# Sheet1.net
KiCad netlist of a schematic drawn in Altium Designer
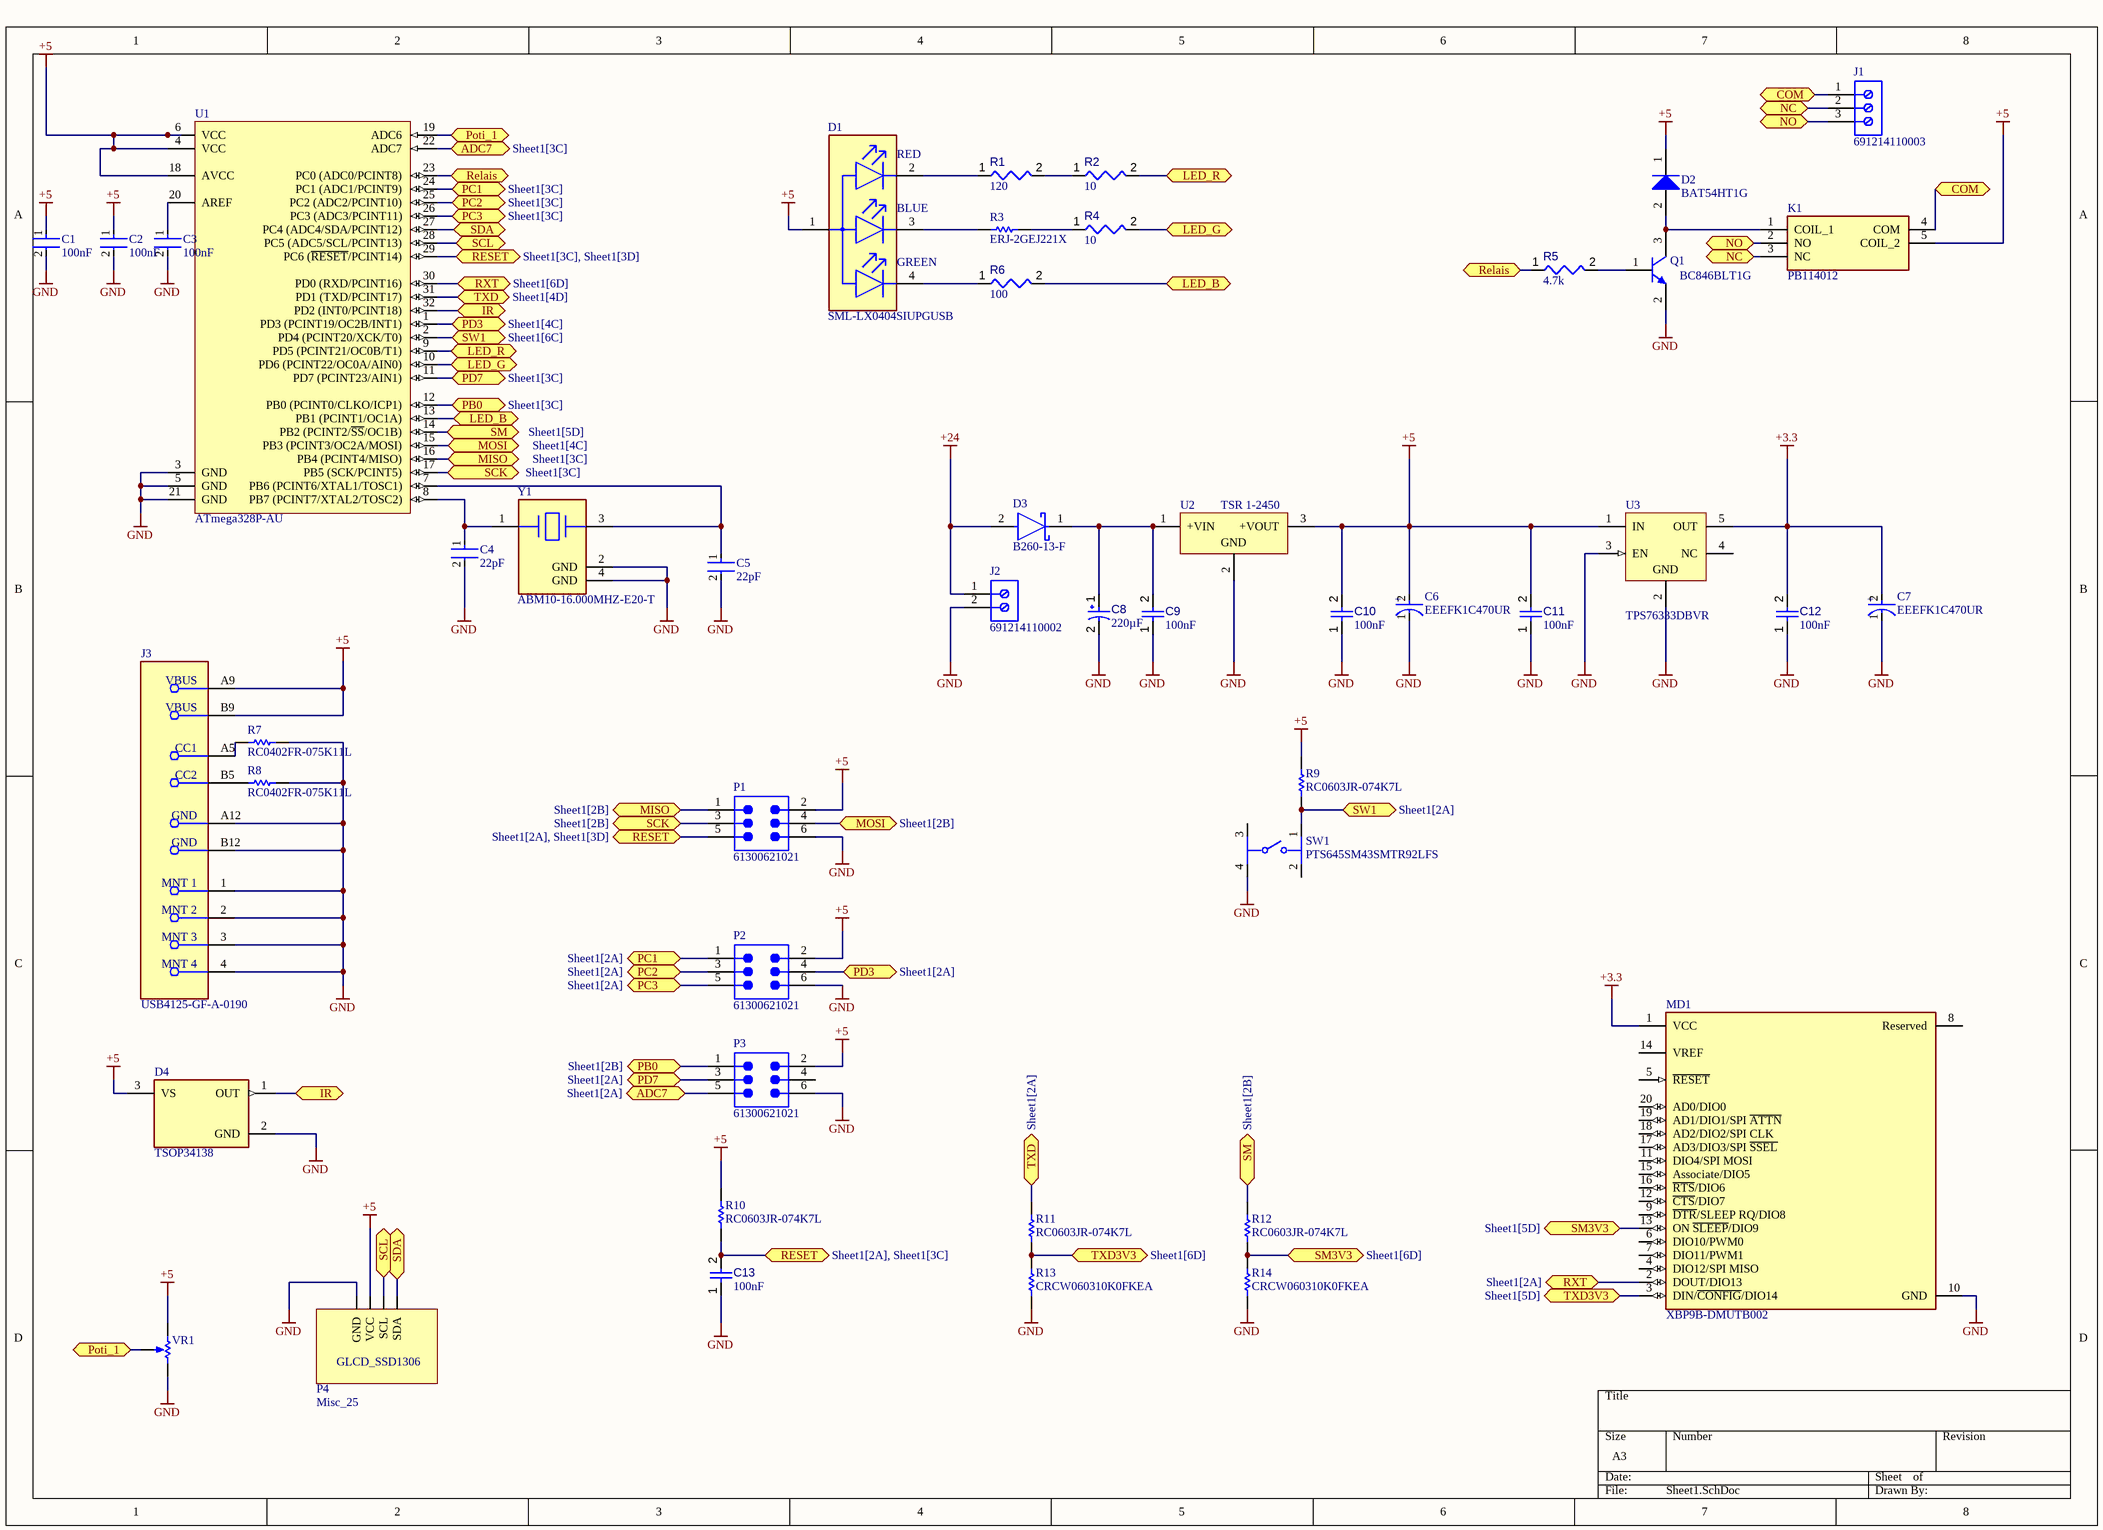
[diagram p0: Sheet1.SchDoc]

(export (version "E")
  (design (tool "Eeschema 10.0.6"))
  (components
    (comp (ref "C1")
      (value "100nF")
      (footprint "FP-C0805C-DN-MFG")
      (description "CAP CER 0.1UF 50V X7R 0805")
      (fields
        (field (name "MANUFACTURER PART NUMBER") "C0805C104K5RACTU")
        (field (name "MANUFACTURER") "KEMET")
      )
      (libsource (lib "Altium Content Vault") (part "b4654b650e69147ec39a6b967a45e02"))
    )
    (comp (ref "C2")
      (value "100nF")
      (footprint "FP-C0805C-DN-MFG")
      (description "CAP CER 0.1UF 50V X7R 0805")
      (fields
        (field (name "MANUFACTURER PART NUMBER") "C0805C104K5RACTU")
        (field (name "MANUFACTURER") "KEMET")
      )
      (libsource (lib "Altium Content Vault") (part "b4654b650e69147ec39a6b967a45e02"))
    )
    (comp (ref "C3")
      (value "100nF")
      (footprint "FP-C0805C-DN-MFG")
      (description "CAP CER 0.1UF 50V X7R 0805")
      (fields
        (field (name "MANUFACTURER PART NUMBER") "C0805C104K5RACTU")
        (field (name "MANUFACTURER") "KEMET")
      )
      (libsource (lib "Altium Content Vault") (part "b4654b650e69147ec39a6b967a45e02"))
    )
    (comp (ref "C4")
      (value "22pF")
      (footprint "FP-C0805C-DN-MFG")
      (description "Capacitor; Ceramic; Cap; 22.0pF; Tol 5%; SMT; Vol-Rtg 50V; C0G; Tape and Reel")
      (fields
        (field (name "OCTOPART") "https://octopart.com/c0805c220j5gactu-kemet-145470")
        (field (name "MANUFACTURER") "KEMET")
      )
      (libsource (lib "Altium Content Vault") (part "b4654b650e69147ec39a6b967a45e02"))
    )
    (comp (ref "C5")
      (value "22pF")
      (footprint "FP-C0805C-DN-MFG")
      (description "Capacitor; Ceramic; Cap; 22.0pF; Tol 5%; SMT; Vol-Rtg 50V; C0G; Tape and Reel")
      (fields
        (field (name "OCTOPART") "https://octopart.com/c0805c220j5gactu-kemet-145470")
        (field (name "MANUFACTURER") "KEMET")
      )
      (libsource (lib "Altium Content Vault") (part "b4654b650e69147ec39a6b967a45e02"))
    )
    (comp (ref "C6")
      (value "EEEFK1C470UR")
      (footprint "FP-FKC-MFG")
      (description "CAP ALUM 47UF 20% 16V SMD")
      (fields (field (name "VOLTAGE") "10V") (field (name "TOLERANCE") "20%"))
      (libsource (lib "Altium Content Vault") (part "cf48714ba7e38822c1575c7ec0b6d1f"))
    )
    (comp (ref "C7")
      (value "EEEFK1C470UR")
      (footprint "FP-FKC-MFG")
      (description "CAP ALUM 47UF 20% 16V SMD")
      (fields (field (name "VOLTAGE") "10V") (field (name "TOLERANCE") "20%"))
      (libsource (lib "Altium Content Vault") (part "cf48714ba7e38822c1575c7ec0b6d1f"))
    )
    (comp (ref "C8")
      (value "220µF")
      (footprint "CAPPR65-500-1250X1000X1350")
      (description "Aluminum Electrolytic Capacitor, 220 uF, +/- 20%, 50 V, -40 to 85 degC, 2-Pin THD, RoHS, Bulk")
      (fields (field (name "MANUFACTURER") "Panasonic") (field (name "TOLERANCE") "20%"))
      (libsource (lib "Lennart Götz") (part "CAP-P-2"))
    )
    (comp (ref "C9")
      (value "100nF")
      (footprint "CAPC0402(1005)60_L")
      (description "Chip Capacitor, 100nF +/-20%, 10V, 0402, Thickness 0.6 mm")
      (fields (field (name "TOLERANCE") "20%") (field (name "Comment") "Capacitor 100nF +/-20% 10V 0402"))
      (libsource (lib "Lennart Götz") (part "CAP-NP-2"))
    )
    (comp (ref "C10")
      (value "100nF")
      (footprint "CAPC0402(1005)60_L")
      (description "Chip Capacitor, 100nF +/-20%, 10V, 0402, Thickness 0.6 mm")
      (fields (field (name "TOLERANCE") "20%") (field (name "Comment") "Capacitor 100nF +/-20% 10V 0402"))
      (libsource (lib "Lennart Götz") (part "CAP-NP-2"))
    )
    (comp (ref "C11")
      (value "100nF")
      (footprint "CAPC0402(1005)60_L")
      (description "Chip Capacitor, 100nF +/-20%, 10V, 0402, Thickness 0.6 mm")
      (fields (field (name "TOLERANCE") "20%") (field (name "Comment") "Capacitor 100nF +/-20% 10V 0402"))
      (libsource (lib "Lennart Götz") (part "CAP-NP-2"))
    )
    (comp (ref "C12")
      (value "100nF")
      (footprint "CAPC0402(1005)60_L")
      (description "Chip Capacitor, 100nF +/-20%, 10V, 0402, Thickness 0.6 mm")
      (fields (field (name "TOLERANCE") "20%") (field (name "Comment") "Capacitor 100nF +/-20% 10V 0402"))
      (libsource (lib "Lennart Götz") (part "CAP-NP-2"))
    )
    (comp (ref "C13")
      (value "100nF")
      (footprint "CAPC0402(1005)60_L")
      (description "Chip Capacitor, 100nF +/-20%, 10V, 0402, Thickness 0.6 mm")
      (fields (field (name "TOLERANCE") "20%") (field (name "Comment") "Capacitor 100nF +/-20% 10V 0402"))
      (libsource (lib "Lennart Götz") (part "CAP-NP-2"))
    )
    (comp (ref "D1")
      (value "SML-LX0404SIUPGUSB")
      (footprint "FP-SML-LX0404SIUPGUSB-MFG")
      (description "LED RGB CLEAR SMD")
      (libsource (lib "Altium Content Vault") (part "2e8871f6955a40d35a6a753e53ead77"))
    )
    (comp (ref "D2")
      (value "BAT54HT1G")
      (footprint "ONSC-SOD-323-2-477-02_V")
      (description "Schottky Barrier Diode, 2-Pin SOD-323, Pb-Free, Tape and Reel")
      (fields (field (name "MANUFACTURER") "On Semiconductor"))
      (libsource (lib "Altium Content Vault") (part "ONSC-D-K1A2-2"))
    )
    (comp (ref "D3")
      (value "B260-13-F")
      (footprint "FP-SMB-MFG")
      (description "DIODE SCHOTTKY 60V 2A SMB")
      (fields
        (field (name "MANUFACTURER") "Diodes Inc.")
        (field (name "OCTOPART") "https://octopart.com/b260-13-f-diodes+inc.-325789")
      )
      (libsource (lib "Altium Content Vault") (part "1d6ec82d83fb6aee721767c19dac4b9"))
    )
    (comp (ref "D4")
      (value "TSOP34138")
      (footprint "FP-6_550-5169_01-4-MFG")
      (description "SENSOR REMOTE REC 38.0KHZ 45M")
      (fields
        (field (name "MANUFACTURER") "Vishay")
        (field (name "OCTOPART") "https://octopart.com/tsop34138-vishay-55433998")
      )
      (libsource (lib "Altium Content Vault") (part "67e88e076711625980e7b323ec594be"))
    )
    (comp (ref "J1")
      (value "691214110003")
      (footprint "691214110003")
      (fields (field (name "VOLTAGE") "300V"))
      (libsource (lib "Altium Content Vault") (part "TBL - 1R - 03P - Screw"))
    )
    (comp (ref "J2")
      (value "691214110002")
      (footprint "691214110002")
      (fields (field (name "VOLTAGE") "300V"))
      (libsource (lib "Altium Content Vault") (part "TBL - 1R - 02P - Screw"))
    )
    (comp (ref "J3")
      (value "USB4125-GF-A-0190")
      (footprint "FP-USB4125-GF-A-0190-MFG")
      (description "CONN RCPT TYPE C 6P SMD RA")
      (libsource (lib "Altium Content Vault") (part "a055484d46e58b234844902c9fd883a"))
    )
    (comp (ref "K1")
      (value "PB114012")
      (footprint "SamacSys:PB134005")
      (description "Relay or Contactor")
      (fields (field (name "MOUSER PART NUMBER") "655-PB114012"))
      (libsource (lib "*") (part "PB114012"))
    )
    (comp (ref "MD1")
      (value "XBP9B-DMUTB002")
      (footprint "FP-XBP9B-DMUTB002-MFG")
      (description "RX TXRX MOD ISM < 1GHZ U.FL TH")
      (libsource (lib "Altium Content Vault") (part "053d8e65a610ce00d52093c0e212ca3"))
    )
    (comp (ref "P1")
      (value "61300621021")
      (footprint "61300621021")
      (libsource (lib "Altium Content Vault") (part "Header_Male_2R_06P"))
    )
    (comp (ref "P2")
      (value "61300621021")
      (footprint "61300621021")
      (libsource (lib "Altium Content Vault") (part "Header_Male_2R_06P"))
    )
    (comp (ref "P3")
      (value "61300621021")
      (footprint "61300621021")
      (libsource (lib "Altium Content Vault") (part "Header_Male_2R_06P"))
    )
    (comp (ref "P4")
      (value "Misc_25")
      (footprint "GLCD_SSD1306")
      (libsource (lib "Lennart Götz") (part "Misc_25"))
    )
    (comp (ref "Q1")
      (value "BC846BLT1G")
      (footprint "ONSC-SOT-23-3-318-08_V")
      (description "General Purpose Transistor, NPN Silicon, 3-Pin SOT-23, Pb-Free, Tape and Reel")
      (fields (field (name "MANUFACTURER") "On Semiconductor"))
      (libsource (lib "Altium Content Vault") (part "ONSC-NPN-B1E2C3-3"))
    )
    (comp (ref "R1")
      (value "120")
      (footprint "RESC0603(1608)_L")
      (description "Chip Resistor, 120 Ohms, +/-5 %, 0.1 W, -55 to 155 degC, 0603")
      (fields (field (name "POWER") "100mW") (field (name "TOLERANCE") "5%"))
      (libsource (lib "Lennart Götz") (part "RES-2"))
    )
    (comp (ref "R2")
      (value "10")
      (footprint "RESC0402(1005)_L")
      (description "Chip Resistor, 10 Ohms, +/-1 %, 63 mW, -55 to 155 degC, 0402")
      (fields (field (name "TOLERANCE") "1%") (field (name "POWER") "63mW"))
      (libsource (lib "Lennart Götz") (part "RES-2"))
    )
    (comp (ref "R3")
      (value "ERJ-2GEJ221X")
      (footprint "RESC1005X40X25LL05T05")
      (description "Chip Resistor, 220 Ohm, +/- 5%, 100 mW, -55 to 155 degC, 0402 (1005 Metric), RoHS, Tape and Reel")
      (fields (field (name "MANUFACTURER") "Basic Passives") (field (name "TOLERANCE") "5%"))
      (libsource (lib "Altium Content Vault") (part "RES-2"))
    )
    (comp (ref "R4")
      (value "10")
      (footprint "RESC0402(1005)_L")
      (description "Chip Resistor, 10 Ohms, +/-1 %, 63 mW, -55 to 155 degC, 0402")
      (fields (field (name "TOLERANCE") "1%") (field (name "POWER") "63mW"))
      (libsource (lib "Lennart Götz") (part "RES-2"))
    )
    (comp (ref "R5")
      (value "4.7k")
      (footprint "RESC2013X70X40ML20T20")
      (description "Chip Resistor, 4.7 KOhm, +/- 1%, 0.125 W, -55 to 155 degC, 0805 (2012 Metric)")
      (fields (field (name "POWER") "125mW") (field (name "TOLERANCE") "1%"))
      (libsource (lib "Lennart Götz") (part "RES-2"))
    )
    (comp (ref "R6")
      (value "100")
      (footprint "RESC0402(1005)_L")
      (description "Chip Resistor, 100 Ohms, +/-1 %, 63 mW, -55 to 155 degC, 0402")
      (fields (field (name "POWER") "63mW") (field (name "TOLERANCE") "1%"))
      (libsource (lib "Lennart Götz") (part "RES-2"))
    )
    (comp (ref "R7")
      (value "RC0402FR-075K11L")
      (footprint "RESC1005X40X25LL05T10")
      (fields (field (name "MANUFACTURER") "Yageo / Phycomp"))
      (libsource (lib "Altium Content Vault") (part "RES"))
    )
    (comp (ref "R8")
      (value "RC0402FR-075K11L")
      (footprint "RESC1005X40X25LL05T10")
      (fields (field (name "MANUFACTURER") "Yageo / Phycomp"))
      (libsource (lib "Altium Content Vault") (part "RES"))
    )
    (comp (ref "R9")
      (value "RC0603JR-074K7L")
      (footprint "RESC1608X55X25ML10T15")
      (description "Chip Resistor, 4.7 KOhm, +/- 5%, 100 mW, -55 to 155 degC, 0603 (1608 Metric), RoHS, Tape and Reel")
      (fields (field (name "TOLERANCE") "5%") (field (name "MANUFACTURER") "Yageo"))
      (libsource (lib "Altium Content Vault") (part "RES-2"))
    )
    (comp (ref "R10")
      (value "RC0603JR-074K7L")
      (footprint "RESC1608X55X25ML10T15")
      (description "Chip Resistor, 4.7 KOhm, +/- 5%, 100 mW, -55 to 155 degC, 0603 (1608 Metric), RoHS, Tape and Reel")
      (fields (field (name "TOLERANCE") "5%") (field (name "MANUFACTURER") "Yageo"))
      (libsource (lib "Altium Content Vault") (part "RES-2"))
    )
    (comp (ref "R11")
      (value "RC0603JR-074K7L")
      (footprint "RESC1608X55X25ML10T15")
      (description "Chip Resistor, 4.7 KOhm, +/- 5%, 100 mW, -55 to 155 degC, 0603 (1608 Metric), RoHS, Tape and Reel")
      (fields (field (name "TOLERANCE") "5%") (field (name "MANUFACTURER") "Yageo"))
      (libsource (lib "Altium Content Vault") (part "RES-2"))
    )
    (comp (ref "R12")
      (value "RC0603JR-074K7L")
      (footprint "RESC1608X55X25ML10T15")
      (description "Chip Resistor, 4.7 KOhm, +/- 5%, 100 mW, -55 to 155 degC, 0603 (1608 Metric), RoHS, Tape and Reel")
      (fields (field (name "TOLERANCE") "5%") (field (name "MANUFACTURER") "Yageo"))
      (libsource (lib "Altium Content Vault") (part "RES-2"))
    )
    (comp (ref "R13")
      (value "CRCW060310K0FKEA")
      (footprint "RESC1609X50X30NL8T20")
      (description "Chip Resistor, 10 KOhm, +/- 1%, 100 mW, -55 to 155 degC, 0603 (1608 Metric), RoHS, Tape and Reel")
      (fields (field (name "MANUFACTURER") "Vishay Semiconductor"))
      (libsource (lib "Altium Content Vault") (part "RES-2"))
    )
    (comp (ref "R14")
      (value "CRCW060310K0FKEA")
      (footprint "RESC1609X50X30NL8T20")
      (description "Chip Resistor, 10 KOhm, +/- 1%, 100 mW, -55 to 155 degC, 0603 (1608 Metric), RoHS, Tape and Reel")
      (fields (field (name "MANUFACTURER") "Vishay Semiconductor"))
      (libsource (lib "Altium Content Vault") (part "RES-2"))
    )
    (comp (ref "SW1")
      (value "PTS645SM43SMTR92LFS")
      (footprint "FP-PTS645SM43SMTR92LFS-MFG")
      (description "SWITCH TACTILE SPST-NO 0.05A 12V")
      (libsource (lib "Altium Content Vault") (part "1adf0dd01260c80cf25a44bfd6b99ba"))
    )
    (comp (ref "U1")
      (value "ATmega328P-AU")
      (footprint "32A_M")
      (libsource (lib "Altium Content Vault") (part "MC-8B-ATM48-SQ32"))
    )
    (comp (ref "U2")
      (value "TSR 1-2450")
      (footprint "TRACO-SIP-3_V")
      (description "DC/DC converter, 5 VDC, 1000 mA, -40 to 85 degC, 3-Pin SIP, RoHS")
      (fields (field (name "MANUFACTURER") "Tracopower"))
      (libsource (lib "Altium Content Vault") (part "TRACO-TSR1-2450-SIP-3"))
    )
    (comp (ref "U3")
      (value "TPS76333DBVR")
      (footprint "DBV0005A_N")
      (fields (field (name "MANUFACTURER") "Texas Instruments"))
      (libsource (lib "Altium Content Vault") (part "TI-TXX7XXXX-5"))
    )
    (comp (ref "VR1")
      (value "3362P-1-103LF")
      (footprint "BOUR-3362P")
      (description "Square Trimpot(R) Trimming Potentiometer, 10 KOhm, 300 V, -55 to 125 degC, 3-Pin THD, RoHS, Tube")
      (fields (field (name "MANUFACTURER") "Bourns") (field (name "TOLERANCE") "10%"))
      (libsource (lib "Lennart Götz") (part "RES-POT-3"))
    )
    (comp (ref "Y1")
      (value "ABM10-16.000MHZ-E20-T")
      (footprint "FP-ABM10-MFG")
      (description "Crystal 16MHz ±20ppm 10pF SMD-4 2.5mm x 2mm")
      (fields (field (name "TOLERANCE") "20ppm"))
      (libsource (lib "Altium Content Vault") (part "0934ba461506c7e3a0bb4df7a4ed385"))
    )
  )
  (nets
    (net (code "1") (name "+3.3") (class "Default")
      (node (ref "C12") (pin "2") (pinfunction "2_2") (pintype "passive"))
      (node (ref "C7") (pin "2") (pinfunction "A_2") (pintype "passive"))
      (node (ref "MD1") (pin "1") (pinfunction "VCC_1") (pintype "power_in"))
      (node (ref "U3") (pin "5") (pinfunction "OUT_5") (pintype "power_in"))
    )
    (net (code "2") (name "+5") (class "Default")
      (node (ref "C1") (pin "1") (pinfunction "1_1") (pintype "passive"))
      (node (ref "C10") (pin "2") (pinfunction "2_2") (pintype "passive"))
      (node (ref "C11") (pin "2") (pinfunction "2_2") (pintype "passive"))
      (node (ref "C2") (pin "1") (pinfunction "1_1") (pintype "passive"))
      (node (ref "C6") (pin "2") (pinfunction "A_2") (pintype "passive"))
      (node (ref "D1") (pin "1") (pinfunction "Common_Anode_1") (pintype "passive"))
      (node (ref "D2") (pin "1") (pinfunction "K_1") (pintype "passive"))
      (node (ref "D4") (pin "3") (pinfunction "VS_3") (pintype "power_in"))
      (node (ref "J3") (pin "A9") (pinfunction "VBUS_A9") (pintype "passive"))
      (node (ref "J3") (pin "B9") (pinfunction "VBUS_B9") (pintype "passive"))
      (node (ref "K1") (pin "5") (pinfunction "COIL_2_5") (pintype "passive"))
      (node (ref "P1") (pin "2") (pinfunction "2_2") (pintype "passive"))
      (node (ref "P2") (pin "2") (pinfunction "2_2") (pintype "passive"))
      (node (ref "P3") (pin "2") (pinfunction "2_2") (pintype "passive"))
      (node (ref "P4") (pin "2") (pinfunction "VCC_2") (pintype "passive"))
      (node (ref "R10") (pin "2") (pinfunction "2_2") (pintype "passive"))
      (node (ref "R9") (pin "2") (pinfunction "2_2") (pintype "passive"))
      (node (ref "U1") (pin "18") (pinfunction "AVCC_18") (pintype "power_in"))
      (node (ref "U1") (pin "4") (pinfunction "VCC_4") (pintype "power_in"))
      (node (ref "U1") (pin "6") (pinfunction "VCC_6") (pintype "power_in"))
      (node (ref "U2") (pin "3") (pinfunction "+VOUT_3") (pintype "power_in"))
      (node (ref "U3") (pin "1") (pinfunction "IN_1") (pintype "power_in"))
      (node (ref "VR1") (pin "1") (pinfunction "CCW_1") (pintype "passive"))
    )
    (net (code "3") (name "+24") (class "Default")
      (node (ref "D3") (pin "2") (pinfunction "A_2") (pintype "passive"))
      (node (ref "J2") (pin "1") (pinfunction "1_1") (pintype "passive"))
    )
    (net (code "4") (name "/ADC7") (class "Default")
      (node (ref "P3") (pin "5") (pinfunction "5_5") (pintype "passive"))
      (node (ref "U1") (pin "22") (pinfunction "ADC7_22") (pintype "input"))
    )
    (net (code "5") (name "/COM") (class "Default")
      (node (ref "J1") (pin "1") (pinfunction "1_1") (pintype "passive"))
      (node (ref "K1") (pin "4") (pinfunction "COM_4") (pintype "passive"))
    )
    (net (code "6") (name "/IR") (class "Default")
      (node (ref "D4") (pin "1") (pinfunction "OUT_1") (pintype "output"))
      (node (ref "U1") (pin "32") (pinfunction "PD2_(INT0/PCINT18)_32") (pintype "bidirectional"))
    )
    (net (code "7") (name "/LED_B") (class "Default")
      (node (ref "R6") (pin "2") (pinfunction "2_2") (pintype "passive"))
      (node (ref "U1") (pin "13") (pinfunction "PB1_(PCINT1/OC1A)_13") (pintype "bidirectional"))
    )
    (net (code "8") (name "/LED_G") (class "Default")
      (node (ref "R4") (pin "2") (pinfunction "2_2") (pintype "passive"))
      (node (ref "U1") (pin "10") (pinfunction "PD6_(PCINT22/OC0A/AIN0)_10") (pintype "bidirectional"))
    )
    (net (code "9") (name "/LED_R") (class "Default")
      (node (ref "R2") (pin "2") (pinfunction "2_2") (pintype "passive"))
      (node (ref "U1") (pin "9") (pinfunction "PD5_(PCINT21/OC0B/T1)_9") (pintype "bidirectional"))
    )
    (net (code "10") (name "/MISO") (class "Default")
      (node (ref "P1") (pin "1") (pinfunction "1_1") (pintype "passive"))
      (node (ref "U1") (pin "16") (pinfunction "PB4_(PCINT4/MISO)_16") (pintype "bidirectional"))
    )
    (net (code "11") (name "/MOSI") (class "Default")
      (node (ref "P1") (pin "4") (pinfunction "4_4") (pintype "passive"))
      (node (ref "U1") (pin "15") (pinfunction "PB3_(PCINT3/OC2A/MOSI)_15") (pintype "bidirectional"))
    )
    (net (code "12") (name "/NC") (class "Default")
      (node (ref "J1") (pin "2") (pinfunction "2_2") (pintype "passive"))
      (node (ref "K1") (pin "3") (pinfunction "NC_3") (pintype "passive"))
    )
    (net (code "13") (name "/NO") (class "Default")
      (node (ref "J1") (pin "3") (pinfunction "3_3") (pintype "passive"))
      (node (ref "K1") (pin "2") (pinfunction "NO_2") (pintype "passive"))
    )
    (net (code "14") (name "/PB0") (class "Default")
      (node (ref "P3") (pin "1") (pinfunction "1_1") (pintype "passive"))
      (node (ref "U1") (pin "12") (pinfunction "PB0_(PCINT0/CLKO/ICP1)_12") (pintype "bidirectional"))
    )
    (net (code "15") (name "/PC1") (class "Default")
      (node (ref "P2") (pin "1") (pinfunction "1_1") (pintype "passive"))
      (node (ref "U1") (pin "24") (pinfunction "PC1_(ADC1/PCINT9)_24") (pintype "bidirectional"))
    )
    (net (code "16") (name "/PC2") (class "Default")
      (node (ref "P2") (pin "3") (pinfunction "3_3") (pintype "passive"))
      (node (ref "U1") (pin "25") (pinfunction "PC2_(ADC2/PCINT10)_25") (pintype "bidirectional"))
    )
    (net (code "17") (name "/PC3") (class "Default")
      (node (ref "P2") (pin "5") (pinfunction "5_5") (pintype "passive"))
      (node (ref "U1") (pin "26") (pinfunction "PC3_(ADC3/PCINT11)_26") (pintype "bidirectional"))
    )
    (net (code "18") (name "/PD3") (class "Default")
      (node (ref "P2") (pin "4") (pinfunction "4_4") (pintype "passive"))
      (node (ref "U1") (pin "1") (pinfunction "PD3_(PCINT19/OC2B/INT1)_1") (pintype "bidirectional"))
    )
    (net (code "19") (name "/PD7") (class "Default")
      (node (ref "P3") (pin "3") (pinfunction "3_3") (pintype "passive"))
      (node (ref "U1") (pin "11") (pinfunction "PD7_(PCINT23/AIN1)_11") (pintype "bidirectional"))
    )
    (net (code "20") (name "/Poti_1") (class "Default")
      (node (ref "U1") (pin "19") (pinfunction "ADC6_19") (pintype "input"))
      (node (ref "VR1") (pin "2") (pinfunction "S_2") (pintype "passive"))
    )
    (net (code "21") (name "/RESET") (class "Default")
      (node (ref "C13") (pin "2") (pinfunction "2_2") (pintype "passive"))
      (node (ref "P1") (pin "5") (pinfunction "5_5") (pintype "passive"))
      (node (ref "R10") (pin "1") (pinfunction "1_1") (pintype "passive"))
      (node (ref "U1") (pin "29") (pinfunction "PC6_(~{RESET}/PCINT14)_29") (pintype "bidirectional"))
    )
    (net (code "22") (name "/RXT") (class "Default")
      (node (ref "MD1") (pin "2") (pinfunction "DOUT/DIO13_2") (pintype "bidirectional"))
      (node (ref "U1") (pin "30") (pinfunction "PD0_(RXD/PCINT16)_30") (pintype "bidirectional"))
    )
    (net (code "23") (name "/Relais") (class "Default")
      (node (ref "R5") (pin "1") (pinfunction "1_1") (pintype "passive"))
      (node (ref "U1") (pin "23") (pinfunction "PC0_(ADC0/PCINT8)_23") (pintype "bidirectional"))
    )
    (net (code "24") (name "/SCK") (class "Default")
      (node (ref "P1") (pin "3") (pinfunction "3_3") (pintype "passive"))
      (node (ref "U1") (pin "17") (pinfunction "PB5_(SCK/PCINT5)_17") (pintype "bidirectional"))
    )
    (net (code "25") (name "/SCL") (class "Default")
      (node (ref "P4") (pin "3") (pinfunction "SCL_3") (pintype "passive"))
      (node (ref "U1") (pin "28") (pinfunction "PC5_(ADC5/SCL/PCINT13)_28") (pintype "bidirectional"))
    )
    (net (code "26") (name "/SDA") (class "Default")
      (node (ref "P4") (pin "4") (pinfunction "SDA_4") (pintype "passive"))
      (node (ref "U1") (pin "27") (pinfunction "PC4_(ADC4/SDA/PCINT12)_27") (pintype "bidirectional"))
    )
    (net (code "27") (name "/SM") (class "Default")
      (node (ref "R12") (pin "2") (pinfunction "2_2") (pintype "passive"))
      (node (ref "U1") (pin "14") (pinfunction "PB2_(PCINT2/~{SS}/OC1B)_14") (pintype "bidirectional"))
    )
    (net (code "28") (name "/SM3V3") (class "Default")
      (node (ref "MD1") (pin "13") (pinfunction "ON_~{SLEEP}/DIO9_13") (pintype "bidirectional"))
      (node (ref "R12") (pin "1") (pinfunction "1_1") (pintype "passive"))
      (node (ref "R14") (pin "2") (pinfunction "2_2") (pintype "passive"))
    )
    (net (code "29") (name "/SW1") (class "Default")
      (node (ref "R9") (pin "1") (pinfunction "1_1") (pintype "passive"))
      (node (ref "SW1") (pin "1") (pinfunction "1_1") (pintype "passive"))
      (node (ref "U1") (pin "2") (pinfunction "PD4_(PCINT20/XCK/T0)_2") (pintype "bidirectional"))
    )
    (net (code "30") (name "/TXD") (class "Default")
      (node (ref "R11") (pin "2") (pinfunction "2_2") (pintype "passive"))
      (node (ref "U1") (pin "31") (pinfunction "PD1_(TXD/PCINT17)_31") (pintype "bidirectional"))
    )
    (net (code "31") (name "/TXD3V3") (class "Default")
      (node (ref "MD1") (pin "3") (pinfunction "DIN/~{CONFIG}/DIO14_3") (pintype "bidirectional"))
      (node (ref "R11") (pin "1") (pinfunction "1_1") (pintype "passive"))
      (node (ref "R13") (pin "2") (pinfunction "2_2") (pintype "passive"))
    )
    (net (code "32") (name "GND") (class "Default")
      (node (ref "C1") (pin "2") (pinfunction "2_2") (pintype "passive"))
      (node (ref "C10") (pin "1") (pinfunction "1_1") (pintype "passive"))
      (node (ref "C11") (pin "1") (pinfunction "1_1") (pintype "passive"))
      (node (ref "C12") (pin "1") (pinfunction "1_1") (pintype "passive"))
      (node (ref "C13") (pin "1") (pinfunction "1_1") (pintype "passive"))
      (node (ref "C2") (pin "2") (pinfunction "2_2") (pintype "passive"))
      (node (ref "C3") (pin "2") (pinfunction "2_2") (pintype "passive"))
      (node (ref "C4") (pin "2") (pinfunction "2_2") (pintype "passive"))
      (node (ref "C5") (pin "2") (pinfunction "2_2") (pintype "passive"))
      (node (ref "C6") (pin "1") (pinfunction "C_1") (pintype "passive"))
      (node (ref "C7") (pin "1") (pinfunction "C_1") (pintype "passive"))
      (node (ref "C8") (pin "2") (pinfunction "2_2") (pintype "passive"))
      (node (ref "C9") (pin "1") (pinfunction "1_1") (pintype "passive"))
      (node (ref "D4") (pin "2") (pinfunction "GND_2") (pintype "power_in"))
      (node (ref "J2") (pin "2") (pinfunction "2_2") (pintype "passive"))
      (node (ref "J3") (pin "1") (pinfunction "MNT_1_1") (pintype "passive"))
      (node (ref "J3") (pin "2") (pinfunction "MNT_2_2") (pintype "passive"))
      (node (ref "J3") (pin "3") (pinfunction "MNT_3_3") (pintype "passive"))
      (node (ref "J3") (pin "4") (pinfunction "MNT_4_4") (pintype "passive"))
      (node (ref "J3") (pin "A12") (pinfunction "GND_A12") (pintype "passive"))
      (node (ref "J3") (pin "B12") (pinfunction "GND_B12") (pintype "passive"))
      (node (ref "MD1") (pin "10") (pinfunction "GND_10") (pintype "power_in"))
      (node (ref "P1") (pin "6") (pinfunction "6_6") (pintype "passive"))
      (node (ref "P2") (pin "6") (pinfunction "6_6") (pintype "passive"))
      (node (ref "P3") (pin "6") (pinfunction "6_6") (pintype "passive"))
      (node (ref "P4") (pin "1") (pinfunction "GND_1") (pintype "passive"))
      (node (ref "Q1") (pin "2") (pinfunction "E_2") (pintype "passive"))
      (node (ref "R13") (pin "1") (pinfunction "1_1") (pintype "passive"))
      (node (ref "R14") (pin "1") (pinfunction "1_1") (pintype "passive"))
      (node (ref "R7") (pin "2") (pinfunction "2_2") (pintype "passive"))
      (node (ref "R8") (pin "2") (pinfunction "2_2") (pintype "passive"))
      (node (ref "SW1") (pin "4") (pinfunction "4_4") (pintype "passive"))
      (node (ref "U1") (pin "21") (pinfunction "GND_21") (pintype "power_in"))
      (node (ref "U1") (pin "3") (pinfunction "GND_3") (pintype "power_in"))
      (node (ref "U1") (pin "5") (pinfunction "GND_5") (pintype "power_in"))
      (node (ref "U2") (pin "2") (pinfunction "GND_2") (pintype "power_in"))
      (node (ref "U3") (pin "2") (pinfunction "GND_2") (pintype "power_in"))
      (node (ref "U3") (pin "3") (pinfunction "EN_3") (pintype "input"))
      (node (ref "VR1") (pin "3") (pinfunction "CW_3") (pintype "passive"))
      (node (ref "Y1") (pin "2") (pinfunction "GND_2") (pintype "power_in"))
      (node (ref "Y1") (pin "4") (pinfunction "GND_4") (pintype "power_in"))
    )
    (net (code "33") (name "Net-(D1-Blue_C)") (class "Default")
      (node (ref "D1") (pin "3") (pinfunction "Blue_C_3") (pintype "passive"))
      (node (ref "R3") (pin "1") (pinfunction "1_1") (pintype "passive"))
    )
    (net (code "34") (name "Net-(D1-Green_C)") (class "Default")
      (node (ref "D1") (pin "4") (pinfunction "Green_C_4") (pintype "passive"))
      (node (ref "R6") (pin "1") (pinfunction "1_1") (pintype "passive"))
    )
    (net (code "35") (name "Net-(D1-Red_C)") (class "Default")
      (node (ref "D1") (pin "2") (pinfunction "Red_C_2") (pintype "passive"))
      (node (ref "R1") (pin "1") (pinfunction "1_1") (pintype "passive"))
    )
    (net (code "36") (name "Net-(D2-A)") (class "Default")
      (node (ref "D2") (pin "2") (pinfunction "A_2") (pintype "passive"))
      (node (ref "K1") (pin "1") (pinfunction "COIL_1_1") (pintype "passive"))
      (node (ref "Q1") (pin "3") (pinfunction "C_3") (pintype "passive"))
    )
    (net (code "37") (name "Net-(D3-C)") (class "Default")
      (node (ref "C8") (pin "1") (pinfunction "1_1") (pintype "passive"))
      (node (ref "C9") (pin "2") (pinfunction "2_2") (pintype "passive"))
      (node (ref "D3") (pin "1") (pinfunction "C_1") (pintype "passive"))
      (node (ref "U2") (pin "1") (pinfunction "+VIN_1") (pintype "power_in"))
    )
    (net (code "38") (name "Net-(J3-CC1)") (class "Default")
      (node (ref "J3") (pin "A5") (pinfunction "CC1_A5") (pintype "passive"))
      (node (ref "R7") (pin "1") (pinfunction "1_1") (pintype "passive"))
    )
    (net (code "39") (name "Net-(J3-CC2)") (class "Default")
      (node (ref "J3") (pin "B5") (pinfunction "CC2_B5") (pintype "passive"))
      (node (ref "R8") (pin "1") (pinfunction "1_1") (pintype "passive"))
    )
    (net (code "40") (name "Net-(Q1-B)") (class "Default")
      (node (ref "Q1") (pin "1") (pinfunction "B_1") (pintype "passive"))
      (node (ref "R5") (pin "2") (pinfunction "2_2") (pintype "passive"))
    )
    (net (code "41") (name "Net-(R1-Pad2)") (class "Default")
      (node (ref "R1") (pin "2") (pinfunction "2_2") (pintype "passive"))
      (node (ref "R2") (pin "1") (pinfunction "1_1") (pintype "passive"))
    )
    (net (code "42") (name "Net-(R3-Pad2)") (class "Default")
      (node (ref "R3") (pin "2") (pinfunction "2_2") (pintype "passive"))
      (node (ref "R4") (pin "1") (pinfunction "1_1") (pintype "passive"))
    )
    (net (code "43") (name "Net-(U1-AREF)") (class "Default")
      (node (ref "C3") (pin "1") (pinfunction "1_1") (pintype "passive"))
      (node (ref "U1") (pin "20") (pinfunction "AREF_20") (pintype "passive"))
    )
    (net (code "44") (name "Net-(U1-PB6_(PCINT6{slash}XTAL1{slash}TOSC1))") (class "Default")
      (node (ref "C5") (pin "1") (pinfunction "1_1") (pintype "passive"))
      (node (ref "U1") (pin "7") (pinfunction "PB6_(PCINT6/XTAL1/TOSC1)_7") (pintype "bidirectional"))
      (node (ref "Y1") (pin "3") (pinfunction "3_3") (pintype "passive"))
    )
    (net (code "45") (name "Net-(U1-PB7_(PCINT7{slash}XTAL2{slash}TOSC2))") (class "Default")
      (node (ref "C4") (pin "1") (pinfunction "1_1") (pintype "passive"))
      (node (ref "U1") (pin "8") (pinfunction "PB7_(PCINT7/XTAL2/TOSC2)_8") (pintype "bidirectional"))
      (node (ref "Y1") (pin "1") (pinfunction "1_1") (pintype "passive"))
    )
    (net (code "46") (name "unconnected-(MD1-AD0{slash}DIO0-Pad20)") (class "Default")
      (node (ref "MD1") (pin "20") (pinfunction "AD0/DIO0_20") (pintype "bidirectional"))
    )
    (net (code "47") (name "unconnected-(MD1-AD1{slash}DIO1{slash}SPI_~{ATTN}-Pad19)") (class "Default")
      (node (ref "MD1") (pin "19") (pinfunction "AD1/DIO1/SPI_~{ATTN}_19") (pintype "bidirectional"))
    )
    (net (code "48") (name "unconnected-(MD1-AD2{slash}DIO2{slash}SPI_CLK-Pad18)") (class "Default")
      (node (ref "MD1") (pin "18") (pinfunction "AD2/DIO2/SPI_CLK_18") (pintype "bidirectional"))
    )
    (net (code "49") (name "unconnected-(MD1-AD3{slash}DIO3{slash}SPI_~{SSEL}-Pad17)") (class "Default")
      (node (ref "MD1") (pin "17") (pinfunction "AD3/DIO3/SPI_~{SSEL}_17") (pintype "bidirectional"))
    )
    (net (code "50") (name "unconnected-(MD1-Associate{slash}DIO5-Pad15)") (class "Default")
      (node (ref "MD1") (pin "15") (pinfunction "Associate/DIO5_15") (pintype "bidirectional"))
    )
    (net (code "51") (name "unconnected-(MD1-DIO4{slash}SPI_MOSI-Pad11)") (class "Default")
      (node (ref "MD1") (pin "11") (pinfunction "DIO4/SPI_MOSI_11") (pintype "bidirectional"))
    )
    (net (code "52") (name "unconnected-(MD1-DIO10{slash}PWM0-Pad6)") (class "Default")
      (node (ref "MD1") (pin "6") (pinfunction "DIO10/PWM0_6") (pintype "bidirectional"))
    )
    (net (code "53") (name "unconnected-(MD1-DIO11{slash}PWM1-Pad7)") (class "Default")
      (node (ref "MD1") (pin "7") (pinfunction "DIO11/PWM1_7") (pintype "bidirectional"))
    )
    (net (code "54") (name "unconnected-(MD1-DIO12{slash}SPI_MISO-Pad4)") (class "Default")
      (node (ref "MD1") (pin "4") (pinfunction "DIO12/SPI_MISO_4") (pintype "bidirectional"))
    )
    (net (code "55") (name "unconnected-(MD1-Reserved-Pad8)") (class "Default")
      (node (ref "MD1") (pin "8") (pinfunction "Reserved_8") (pintype "passive"))
    )
    (net (code "56") (name "unconnected-(MD1-VREF-Pad14)") (class "Default")
      (node (ref "MD1") (pin "14") (pinfunction "VREF_14") (pintype "passive"))
    )
    (net (code "57") (name "unconnected-(MD1-~{CTS}{slash}DIO7-Pad12)") (class "Default")
      (node (ref "MD1") (pin "12") (pinfunction "~{CTS}/DIO7_12") (pintype "bidirectional"))
    )
    (net (code "58") (name "unconnected-(MD1-~{DTR}{slash}SLEEP_RQ{slash}DIO8-Pad9)") (class "Default")
      (node (ref "MD1") (pin "9") (pinfunction "~{DTR}/SLEEP_RQ/DIO8_9") (pintype "bidirectional"))
    )
    (net (code "59") (name "unconnected-(MD1-~{RESET}-Pad5)") (class "Default")
      (node (ref "MD1") (pin "5") (pinfunction "~{RESET}_5") (pintype "input"))
    )
    (net (code "60") (name "unconnected-(MD1-~{RTS}{slash}DIO6-Pad16)") (class "Default")
      (node (ref "MD1") (pin "16") (pinfunction "~{RTS}/DIO6_16") (pintype "bidirectional"))
    )
    (net (code "61") (name "unconnected-(P3-Pad4)") (class "Default")
      (node (ref "P3") (pin "4") (pinfunction "4_4") (pintype "passive"))
    )
    (net (code "62") (name "unconnected-(SW1-Pad2)") (class "Default")
      (node (ref "SW1") (pin "2") (pinfunction "2_2") (pintype "passive"))
    )
    (net (code "63") (name "unconnected-(SW1-Pad3)") (class "Default")
      (node (ref "SW1") (pin "3") (pinfunction "3_3") (pintype "passive"))
    )
    (net (code "64") (name "unconnected-(U3-NC-Pad4)") (class "Default")
      (node (ref "U3") (pin "4") (pinfunction "NC_4") (pintype "passive"))
    )
  )
)
